# 1uO_c_v_2_2.net
KiCad netlist of a schematic drawn in EAGLE
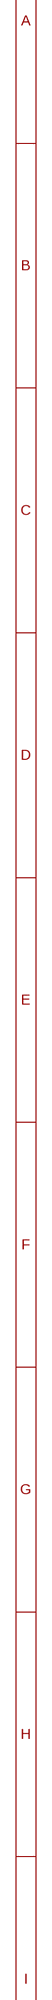
[diagram p0: schematic, sheet 1, part 1 of 2]
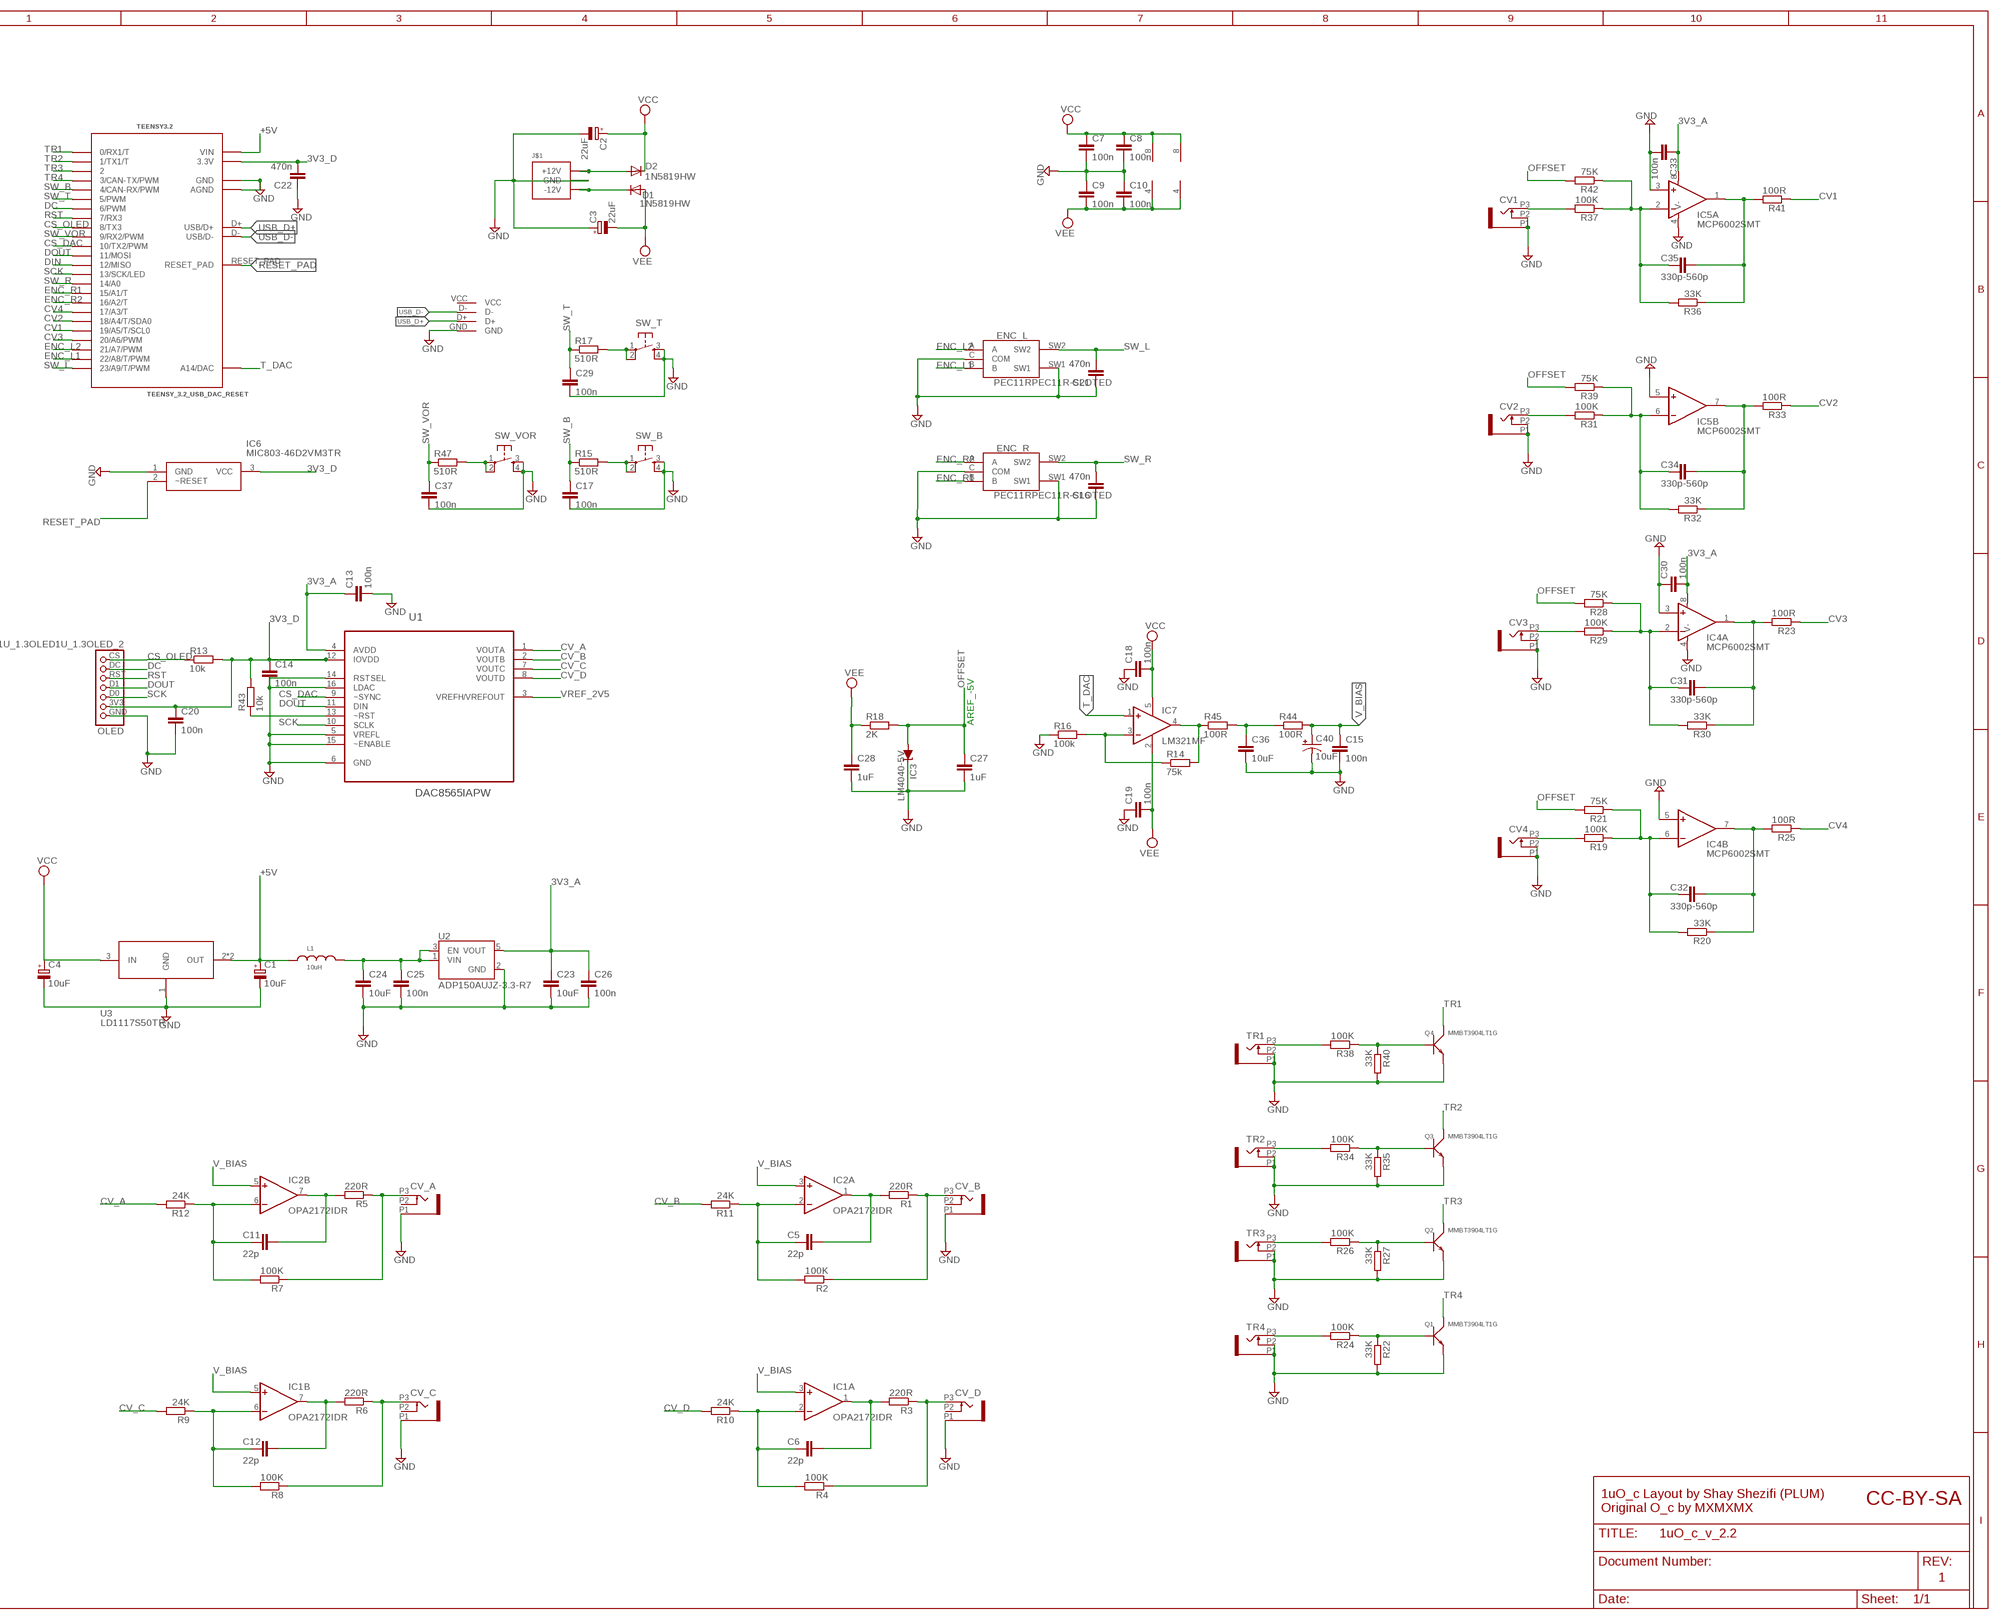
[diagram p1: schematic, sheet 1, part 2 of 2]

(export (version "E")
  (design (tool "Eeschema 10.0.6"))
  (components
    (comp (ref "C1")
      (value "10uF")
      (footprint "eagle-import:PANASONIC_B")
      (libsource (lib "eagle-import") (part "CPOL-EUB"))
    )
    (comp (ref "C2")
      (value "22uF")
      (footprint "eagle-import:PANASONIC_C")
      (libsource (lib "eagle-import") (part "CPOL-EUC"))
    )
    (comp (ref "C3")
      (value "22uF")
      (footprint "eagle-import:PANASONIC_C")
      (libsource (lib "eagle-import") (part "CPOL-EUC"))
    )
    (comp (ref "C4")
      (value "10uF")
      (footprint "eagle-import:PANASONIC_B")
      (libsource (lib "eagle-import") (part "CPOL-EUB"))
    )
    (comp (ref "C5")
      (value "22p")
      (footprint "eagle-import:C0603")
      (libsource (lib "eagle-import") (part "C-EUC0603"))
    )
    (comp (ref "C6")
      (value "22p")
      (footprint "eagle-import:C0603")
      (libsource (lib "eagle-import") (part "C-EUC0603"))
    )
    (comp (ref "C7")
      (value "100n")
      (footprint "eagle-import:C0603")
      (libsource (lib "eagle-import") (part "C-EUC0603"))
    )
    (comp (ref "C8")
      (value "100n")
      (footprint "eagle-import:C0603")
      (libsource (lib "eagle-import") (part "C-EUC0603"))
    )
    (comp (ref "C9")
      (value "100n")
      (footprint "eagle-import:C0603")
      (libsource (lib "eagle-import") (part "C-EUC0603"))
    )
    (comp (ref "C10")
      (value "100n")
      (footprint "eagle-import:C0603")
      (libsource (lib "eagle-import") (part "C-EUC0603"))
    )
    (comp (ref "C11")
      (value "22p")
      (footprint "eagle-import:C0603")
      (libsource (lib "eagle-import") (part "C-EUC0603"))
    )
    (comp (ref "C12")
      (value "22p")
      (footprint "eagle-import:C0603")
      (libsource (lib "eagle-import") (part "C-EUC0603"))
    )
    (comp (ref "C13")
      (value "100n")
      (footprint "eagle-import:C0603")
      (libsource (lib "eagle-import") (part "C-EUC0603"))
    )
    (comp (ref "C14")
      (value "100n")
      (footprint "eagle-import:C0603")
      (libsource (lib "eagle-import") (part "C-EUC0603"))
    )
    (comp (ref "C15")
      (value "100n")
      (footprint "eagle-import:C0603")
      (libsource (lib "eagle-import") (part "C-EUC0603"))
    )
    (comp (ref "C16")
      (value "470n")
      (footprint "eagle-import:C0603")
      (libsource (lib "eagle-import") (part "C-EUC0603"))
    )
    (comp (ref "C17")
      (value "100n")
      (footprint "eagle-import:C0603")
      (libsource (lib "eagle-import") (part "C-EUC0603"))
    )
    (comp (ref "C18")
      (value "100n")
      (footprint "eagle-import:C0603")
      (libsource (lib "eagle-import") (part "C-EUC0603"))
    )
    (comp (ref "C19")
      (value "100n")
      (footprint "eagle-import:C0603")
      (libsource (lib "eagle-import") (part "C-EUC0603"))
    )
    (comp (ref "C20")
      (value "100n")
      (footprint "eagle-import:C0603")
      (libsource (lib "eagle-import") (part "C-EUC0603"))
    )
    (comp (ref "C21")
      (value "470n")
      (footprint "eagle-import:C0603")
      (libsource (lib "eagle-import") (part "C-EUC0603"))
    )
    (comp (ref "C22")
      (value "470n")
      (footprint "eagle-import:C0603")
      (libsource (lib "eagle-import") (part "C-EUC0603"))
    )
    (comp (ref "C23")
      (value "10uF")
      (footprint "eagle-import:C1206K")
      (libsource (lib "eagle-import") (part "C-EUC1206K"))
    )
    (comp (ref "C24")
      (value "10uF")
      (footprint "eagle-import:C1206K")
      (libsource (lib "eagle-import") (part "C-EUC1206K"))
    )
    (comp (ref "C25")
      (value "100n")
      (footprint "eagle-import:C0603")
      (libsource (lib "eagle-import") (part "C-EUC0603"))
    )
    (comp (ref "C26")
      (value "100n")
      (footprint "eagle-import:C0603")
      (libsource (lib "eagle-import") (part "C-EUC0603"))
    )
    (comp (ref "C27")
      (value "1uF")
      (footprint "eagle-import:C0603")
      (libsource (lib "eagle-import") (part "C-EUC0603"))
    )
    (comp (ref "C28")
      (value "1uF")
      (footprint "eagle-import:C0603")
      (libsource (lib "eagle-import") (part "C-EUC0603"))
    )
    (comp (ref "C29")
      (value "100n")
      (footprint "eagle-import:C0603")
      (libsource (lib "eagle-import") (part "C-EUC0603"))
    )
    (comp (ref "C30")
      (value "100n")
      (footprint "eagle-import:C0603")
      (libsource (lib "eagle-import") (part "C-EUC0603"))
    )
    (comp (ref "C31")
      (value "330p-560p")
      (footprint "eagle-import:C0603")
      (libsource (lib "eagle-import") (part "C-EUC0603"))
    )
    (comp (ref "C32")
      (value "330p-560p")
      (footprint "eagle-import:C0603")
      (libsource (lib "eagle-import") (part "C-EUC0603"))
    )
    (comp (ref "C33")
      (value "100n")
      (footprint "eagle-import:C0603")
      (libsource (lib "eagle-import") (part "C-EUC0603"))
    )
    (comp (ref "C34")
      (value "330p-560p")
      (footprint "eagle-import:C0603")
      (libsource (lib "eagle-import") (part "C-EUC0603"))
    )
    (comp (ref "C35")
      (value "330p-560p")
      (footprint "eagle-import:C0603")
      (libsource (lib "eagle-import") (part "C-EUC0603"))
    )
    (comp (ref "C36")
      (value "10uF")
      (footprint "eagle-import:C0603")
      (libsource (lib "eagle-import") (part "C-EUC0603"))
    )
    (comp (ref "C37")
      (value "100n")
      (footprint "eagle-import:C0603")
      (libsource (lib "eagle-import") (part "C-EUC0603"))
    )
    (comp (ref "C40")
      (value "10uF")
      (footprint "eagle-import:PANASONIC_A")
      (libsource (lib "eagle-import") (part "CPOL-USA"))
    )
    (comp (ref "CV1")
      (value "OG-PJ301_PJ301_THONKICONN")
      (footprint "eagle-import:OG-PJ301_WQP_PJ_301M6_NO_HOLE")
      (libsource (lib "eagle-import") (part "OG-PJ301_PJ301_THONKICONN"))
    )
    (comp (ref "CV2")
      (value "OG-PJ301_PJ301_THONKICONN")
      (footprint "eagle-import:OG-PJ301_WQP_PJ_301M6_NO_HOLE")
      (libsource (lib "eagle-import") (part "OG-PJ301_PJ301_THONKICONN"))
    )
    (comp (ref "CV3")
      (value "OG-PJ301_PJ301_THONKICONN")
      (footprint "eagle-import:OG-PJ301_WQP_PJ_301M6_NO_HOLE")
      (libsource (lib "eagle-import") (part "OG-PJ301_PJ301_THONKICONN"))
    )
    (comp (ref "CV4")
      (value "OG-PJ301_PJ301_THONKICONN")
      (footprint "eagle-import:OG-PJ301_WQP_PJ_301M6_NO_HOLE")
      (libsource (lib "eagle-import") (part "OG-PJ301_PJ301_THONKICONN"))
    )
    (comp (ref "CV_A")
      (value "OG-PJ301_PJ301_THONKICONN")
      (footprint "eagle-import:OG-PJ301_WQP_PJ_301M6_NO_HOLE")
      (libsource (lib "eagle-import") (part "OG-PJ301_PJ301_THONKICONN"))
    )
    (comp (ref "CV_B")
      (value "OG-PJ301_PJ301_THONKICONN")
      (footprint "eagle-import:OG-PJ301_WQP_PJ_301M6_NO_HOLE")
      (libsource (lib "eagle-import") (part "OG-PJ301_PJ301_THONKICONN"))
    )
    (comp (ref "CV_C")
      (value "OG-PJ301_PJ301_THONKICONN")
      (footprint "eagle-import:OG-PJ301_WQP_PJ_301M6_NO_HOLE")
      (libsource (lib "eagle-import") (part "OG-PJ301_PJ301_THONKICONN"))
    )
    (comp (ref "CV_D")
      (value "OG-PJ301_PJ301_THONKICONN")
      (footprint "eagle-import:OG-PJ301_WQP_PJ_301M6_NO_HOLE")
      (libsource (lib "eagle-import") (part "OG-PJ301_PJ301_THONKICONN"))
    )
    (comp (ref "D1")
      (value "1N5819HW")
      (footprint "eagle-import:DIODE_SOD123")
      (libsource (lib "eagle-import") (part "DIODE_DIODE-SOD123"))
    )
    (comp (ref "D2")
      (value "1N5819HW")
      (footprint "eagle-import:DIODE_SOD123")
      (libsource (lib "eagle-import") (part "DIODE_DIODE-SOD123"))
    )
    (comp (ref "ENC_L")
      (value "PEC11RPEC11R-SLOTED")
      (footprint "eagle-import:PEC11R-SLOTED")
      (libsource (lib "eagle-import") (part "PEC11RPEC11R-SLOTED"))
    )
    (comp (ref "ENC_R")
      (value "PEC11RPEC11R-SLOTED")
      (footprint "eagle-import:PEC11R-SLOTED")
      (libsource (lib "eagle-import") (part "PEC11RPEC11R-SLOTED"))
    )
    (comp (ref "IC1")
      (value "OPA2172IDR")
      (footprint "eagle-import:SO08")
      (libsource (lib "eagle-import") (part "TL072D"))
    )
    (comp (ref "IC2")
      (value "OPA2172IDR")
      (footprint "eagle-import:SO08")
      (libsource (lib "eagle-import") (part "TL072D"))
    )
    (comp (ref "IC3")
      (value "LM4040-5V")
      (footprint "eagle-import:DBZ_R-PDSO-G3")
      (libsource (lib "eagle-import") (part "LM4041DBZB12"))
    )
    (comp (ref "IC4")
      (value "MCP6002SMT")
      (footprint "eagle-import:SOIC8")
      (libsource (lib "eagle-import") (part "MCP6002SMT"))
    )
    (comp (ref "IC5")
      (value "MCP6002SMT")
      (footprint "eagle-import:SOIC8")
      (libsource (lib "eagle-import") (part "MCP6002SMT"))
    )
    (comp (ref "IC6")
      (value "MIC803-46D2VM3TR")
      (footprint "eagle-import:SOT95P230X110-3N")
      (libsource (lib "eagle-import") (part "MIC803-46D2VM3TR"))
    )
    (comp (ref "IC7")
      (value "LM321MF")
      (footprint "eagle-import:SOT23-5")
      (libsource (lib "eagle-import") (part "LM321?MF"))
    )
    (comp (ref "J$1")
      (value "POWER_SIMPLE10")
      (footprint "eagle-import:POWER_10")
      (libsource (lib "eagle-import") (part "POWER_SIMPLE10"))
    )
    (comp (ref "L1")
      (value "10uH")
      (footprint "eagle-import:WE-LQ_M")
      (libsource (lib "eagle-import") (part "WE-LQ_1210_744032001"))
    )
    (comp (ref "OLED")
      (value "1U_1.3OLED1U_1.3OLED_2")
      (footprint "eagle-import:1U_1.3OLED_2")
      (libsource (lib "eagle-import") (part "1U_1.3OLED1U_1.3OLED_2"))
    )
    (comp (ref "Q1")
      (value "MMBT3904LT1G")
      (footprint "eagle-import:SOT-23")
      (libsource (lib "eagle-import") (part "SMD-TRANSISTORS-NPN-40V-200MA-MMBT3904LT1G(SOT-23)"))
    )
    (comp (ref "Q2")
      (value "MMBT3904LT1G")
      (footprint "eagle-import:SOT-23")
      (libsource (lib "eagle-import") (part "SMD-TRANSISTORS-NPN-40V-200MA-MMBT3904LT1G(SOT-23)"))
    )
    (comp (ref "Q3")
      (value "MMBT3904LT1G")
      (footprint "eagle-import:SOT-23")
      (libsource (lib "eagle-import") (part "SMD-TRANSISTORS-NPN-40V-200MA-MMBT3904LT1G(SOT-23)"))
    )
    (comp (ref "Q4")
      (value "MMBT3904LT1G")
      (footprint "eagle-import:SOT-23")
      (libsource (lib "eagle-import") (part "SMD-TRANSISTORS-NPN-40V-200MA-MMBT3904LT1G(SOT-23)"))
    )
    (comp (ref "R1")
      (value "220R")
      (footprint "eagle-import:R0603")
      (libsource (lib "eagle-import") (part "R-EU_R0603"))
    )
    (comp (ref "R2")
      (value "100K")
      (footprint "eagle-import:R0603")
      (libsource (lib "eagle-import") (part "R-EU_R0603"))
    )
    (comp (ref "R3")
      (value "220R")
      (footprint "eagle-import:R0603")
      (libsource (lib "eagle-import") (part "R-EU_R0603"))
    )
    (comp (ref "R4")
      (value "100K")
      (footprint "eagle-import:R0603")
      (libsource (lib "eagle-import") (part "R-EU_R0603"))
    )
    (comp (ref "R5")
      (value "220R")
      (footprint "eagle-import:R0603")
      (libsource (lib "eagle-import") (part "R-EU_R0603"))
    )
    (comp (ref "R6")
      (value "220R")
      (footprint "eagle-import:R0603")
      (libsource (lib "eagle-import") (part "R-EU_R0603"))
    )
    (comp (ref "R7")
      (value "100K")
      (footprint "eagle-import:R0603")
      (libsource (lib "eagle-import") (part "R-EU_R0603"))
    )
    (comp (ref "R8")
      (value "100K")
      (footprint "eagle-import:R0603")
      (libsource (lib "eagle-import") (part "R-EU_R0603"))
    )
    (comp (ref "R9")
      (value "24K")
      (footprint "eagle-import:R0603")
      (libsource (lib "eagle-import") (part "R-EU_R0603"))
    )
    (comp (ref "R10")
      (value "24K")
      (footprint "eagle-import:R0603")
      (libsource (lib "eagle-import") (part "R-EU_R0603"))
    )
    (comp (ref "R11")
      (value "24K")
      (footprint "eagle-import:R0603")
      (libsource (lib "eagle-import") (part "R-EU_R0603"))
    )
    (comp (ref "R12")
      (value "24K")
      (footprint "eagle-import:R0603")
      (libsource (lib "eagle-import") (part "R-EU_R0603"))
    )
    (comp (ref "R13")
      (value "10k")
      (footprint "eagle-import:R0603")
      (libsource (lib "eagle-import") (part "R-EU_R0603"))
    )
    (comp (ref "R14")
      (value "75k")
      (footprint "eagle-import:R0603")
      (libsource (lib "eagle-import") (part "R-EU_R0603"))
    )
    (comp (ref "R15")
      (value "510R")
      (footprint "eagle-import:R0603")
      (libsource (lib "eagle-import") (part "R-EU_R0603"))
    )
    (comp (ref "R16")
      (value "100k")
      (footprint "eagle-import:R0603")
      (libsource (lib "eagle-import") (part "R-EU_R0603"))
    )
    (comp (ref "R17")
      (value "510R")
      (footprint "eagle-import:R0603")
      (libsource (lib "eagle-import") (part "R-EU_R0603"))
    )
    (comp (ref "R18")
      (value "2K")
      (footprint "eagle-import:R0603")
      (libsource (lib "eagle-import") (part "R-EU_R0603"))
    )
    (comp (ref "R19")
      (value "100K")
      (footprint "eagle-import:R0603")
      (libsource (lib "eagle-import") (part "R-EU_R0603"))
    )
    (comp (ref "R20")
      (value "33K")
      (footprint "eagle-import:R0603")
      (libsource (lib "eagle-import") (part "R-EU_R0603"))
    )
    (comp (ref "R21")
      (value "75K")
      (footprint "eagle-import:R0603")
      (libsource (lib "eagle-import") (part "R-EU_R0603"))
    )
    (comp (ref "R22")
      (value "33K")
      (footprint "eagle-import:R0603")
      (libsource (lib "eagle-import") (part "R-EU_R0603"))
    )
    (comp (ref "R23")
      (value "100R")
      (footprint "eagle-import:R0603")
      (libsource (lib "eagle-import") (part "R-EU_R0603"))
    )
    (comp (ref "R24")
      (value "100K")
      (footprint "eagle-import:R0603")
      (libsource (lib "eagle-import") (part "R-EU_R0603"))
    )
    (comp (ref "R25")
      (value "100R")
      (footprint "eagle-import:R0603")
      (libsource (lib "eagle-import") (part "R-EU_R0603"))
    )
    (comp (ref "R26")
      (value "100K")
      (footprint "eagle-import:R0603")
      (libsource (lib "eagle-import") (part "R-EU_R0603"))
    )
    (comp (ref "R27")
      (value "33K")
      (footprint "eagle-import:R0603")
      (libsource (lib "eagle-import") (part "R-EU_R0603"))
    )
    (comp (ref "R28")
      (value "75K")
      (footprint "eagle-import:R0603")
      (libsource (lib "eagle-import") (part "R-EU_R0603"))
    )
    (comp (ref "R29")
      (value "100K")
      (footprint "eagle-import:R0603")
      (libsource (lib "eagle-import") (part "R-EU_R0603"))
    )
    (comp (ref "R30")
      (value "33K")
      (footprint "eagle-import:R0603")
      (libsource (lib "eagle-import") (part "R-EU_R0603"))
    )
    (comp (ref "R31")
      (value "100K")
      (footprint "eagle-import:R0603")
      (libsource (lib "eagle-import") (part "R-EU_R0603"))
    )
    (comp (ref "R32")
      (value "33K")
      (footprint "eagle-import:R0603")
      (libsource (lib "eagle-import") (part "R-EU_R0603"))
    )
    (comp (ref "R33")
      (value "100R")
      (footprint "eagle-import:R0603")
      (libsource (lib "eagle-import") (part "R-EU_R0603"))
    )
    (comp (ref "R34")
      (value "100K")
      (footprint "eagle-import:R0603")
      (libsource (lib "eagle-import") (part "R-EU_R0603"))
    )
    (comp (ref "R35")
      (value "33K")
      (footprint "eagle-import:R0603")
      (libsource (lib "eagle-import") (part "R-EU_R0603"))
    )
    (comp (ref "R36")
      (value "33K")
      (footprint "eagle-import:R0603")
      (libsource (lib "eagle-import") (part "R-EU_R0603"))
    )
    (comp (ref "R37")
      (value "100K")
      (footprint "eagle-import:R0603")
      (libsource (lib "eagle-import") (part "R-EU_R0603"))
    )
    (comp (ref "R38")
      (value "100K")
      (footprint "eagle-import:R0603")
      (libsource (lib "eagle-import") (part "R-EU_R0603"))
    )
    (comp (ref "R39")
      (value "75K")
      (footprint "eagle-import:R0603")
      (libsource (lib "eagle-import") (part "R-EU_R0603"))
    )
    (comp (ref "R40")
      (value "33K")
      (footprint "eagle-import:R0603")
      (libsource (lib "eagle-import") (part "R-EU_R0603"))
    )
    (comp (ref "R41")
      (value "100R")
      (footprint "eagle-import:R0603")
      (libsource (lib "eagle-import") (part "R-EU_R0603"))
    )
    (comp (ref "R42")
      (value "75K")
      (footprint "eagle-import:R0603")
      (libsource (lib "eagle-import") (part "R-EU_R0603"))
    )
    (comp (ref "R43")
      (value "10k")
      (footprint "eagle-import:R0603")
      (libsource (lib "eagle-import") (part "R-EU_R0603"))
    )
    (comp (ref "R44")
      (value "100R")
      (footprint "eagle-import:R0603")
      (libsource (lib "eagle-import") (part "R-EU_R0603"))
    )
    (comp (ref "R45")
      (value "100R")
      (footprint "eagle-import:R0603")
      (libsource (lib "eagle-import") (part "R-EU_R0603"))
    )
    (comp (ref "R47")
      (value "510R")
      (footprint "eagle-import:R0603")
      (libsource (lib "eagle-import") (part "R-EU_R0603"))
    )
    (comp (ref "SW_B")
      (value "TAC_SWITCHPTH")
      (footprint "eagle-import:TACTILE-PTH")
      (libsource (lib "eagle-import") (part "TAC_SWITCHPTH"))
    )
    (comp (ref "SW_T")
      (value "TAC_SWITCHPTH")
      (footprint "eagle-import:TACTILE-PTH")
      (libsource (lib "eagle-import") (part "TAC_SWITCHPTH"))
    )
    (comp (ref "SW_VOR")
      (value "TAC_SWITCHPTH")
      (footprint "eagle-import:TACTILE-PTH")
      (libsource (lib "eagle-import") (part "TAC_SWITCHPTH"))
    )
    (comp (ref "TEENSY3.2")
      (value "TEENSY_3.2_USB_DAC_RESET")
      (footprint "eagle-import:TEENSY_3.2_USB_DAC_RESET")
      (libsource (lib "eagle-import") (part "TEENSY_3.2_USB_DAC_RESET"))
    )
    (comp (ref "TR1")
      (value "OG-PJ301_PJ301_THONKICONN")
      (footprint "eagle-import:OG-PJ301_WQP_PJ_301M6_NO_HOLE")
      (libsource (lib "eagle-import") (part "OG-PJ301_PJ301_THONKICONN"))
    )
    (comp (ref "TR2")
      (value "OG-PJ301_PJ301_THONKICONN")
      (footprint "eagle-import:OG-PJ301_WQP_PJ_301M6_NO_HOLE")
      (libsource (lib "eagle-import") (part "OG-PJ301_PJ301_THONKICONN"))
    )
    (comp (ref "TR3")
      (value "OG-PJ301_PJ301_THONKICONN")
      (footprint "eagle-import:OG-PJ301_WQP_PJ_301M6_NO_HOLE")
      (libsource (lib "eagle-import") (part "OG-PJ301_PJ301_THONKICONN"))
    )
    (comp (ref "TR4")
      (value "OG-PJ301_PJ301_THONKICONN")
      (footprint "eagle-import:OG-PJ301_WQP_PJ_301M6_NO_HOLE")
      (libsource (lib "eagle-import") (part "OG-PJ301_PJ301_THONKICONN"))
    )
    (comp (ref "U$1")
      (value "USB_BOARD")
      (footprint "eagle-import:MICRO-USB-BOARD")
      (libsource (lib "eagle-import") (part "USB_BOARD"))
    )
    (comp (ref "U1")
      (value "DAC8565IAPW")
      (footprint "eagle-import:SOP65P640X120-16N")
      (fields (field (name "MF") "Texas Instruments"))
      (libsource (lib "eagle-import") (part "DAC8565IAPW"))
    )
    (comp (ref "U2")
      (value "ADP150AUJZ-3.3-R7")
      (footprint "eagle-import:SOT95P280X100-5N")
      (fields (field (name "MF") "Analog Devices") (field (name "MP") "ADP150AUJZ-2.0-R7"))
      (libsource (lib "eagle-import") (part "ADP150AUJZ-3.3-R7"))
    )
    (comp (ref "U3")
      (value "LD1117S50TR")
      (footprint "eagle-import:SOT223")
      (fields (field (name "MF") "STMicroelectronics"))
      (libsource (lib "eagle-import") (part "LD1117S50TR"))
    )
  )
  (nets
    (net (code "1") (name "/+5V") (class "Default")
      (node (ref "C1") (pin "+") (pinfunction "+_+") (pintype "passive"))
      (node (ref "L1") (pin "1") (pinfunction "1_1") (pintype "passive"))
      (node (ref "TEENSY3.2") (pin "VIN") (pinfunction "VIN_VIN") (pintype "power_in"))
      (node (ref "U3") (pin "2") (pinfunction "OUT_2") (pintype "output"))
      (node (ref "U3") (pin "4") (pinfunction "OUT_4") (pintype "output"))
    )
    (net (code "2") (name "/3V3_A") (class "Default")
      (node (ref "C13") (pin "1") (pinfunction "1_1") (pintype "passive"))
      (node (ref "C23") (pin "1") (pinfunction "1_1") (pintype "passive"))
      (node (ref "C26") (pin "1") (pinfunction "1_1") (pintype "passive"))
      (node (ref "C30") (pin "2") (pinfunction "2_2") (pintype "passive"))
      (node (ref "C33") (pin "1") (pinfunction "1_1") (pintype "passive"))
      (node (ref "IC4") (pin "8") (pinfunction "V+_8") (pintype "power_in"))
      (node (ref "IC5") (pin "8") (pinfunction "V+_8") (pintype "power_in"))
      (node (ref "U1") (pin "4") (pinfunction "AVDD_4") (pintype "power_in"))
      (node (ref "U2") (pin "5") (pinfunction "VOUT_5") (pintype "output"))
    )
    (net (code "3") (name "/3V3_D") (class "Default")
      (node (ref "C14") (pin "1") (pinfunction "1_1") (pintype "passive"))
      (node (ref "C20") (pin "1") (pinfunction "1_1") (pintype "passive"))
      (node (ref "C22") (pin "2") (pinfunction "2_2") (pintype "passive"))
      (node (ref "IC6") (pin "3") (pinfunction "VCC_3") (pintype "bidirectional"))
      (node (ref "OLED") (pin "3V3") (pinfunction "3V3_3V3") (pintype "passive"))
      (node (ref "R13") (pin "2") (pinfunction "2_2") (pintype "passive"))
      (node (ref "R43") (pin "2") (pinfunction "2_2") (pintype "passive"))
      (node (ref "TEENSY3.2") (pin "3.3V") (pinfunction "3.3V_3.3V") (pintype "power_in"))
      (node (ref "U1") (pin "12") (pinfunction "IOVDD_12") (pintype "power_in"))
    )
    (net (code "4") (name "/CS_DAC") (class "Default")
      (node (ref "TEENSY3.2") (pin "10") (pinfunction "10/TX2/PWM_10") (pintype "bidirectional"))
      (node (ref "U1") (pin "9") (pinfunction "~{SYNC}_9") (pintype "input"))
    )
    (net (code "5") (name "/CS_OLED") (class "Default")
      (node (ref "OLED") (pin "CS") (pinfunction "CS_CS") (pintype "passive"))
      (node (ref "R13") (pin "1") (pinfunction "1_1") (pintype "passive"))
      (node (ref "TEENSY3.2") (pin "8") (pinfunction "8/TX3_8") (pintype "bidirectional"))
    )
    (net (code "6") (name "/CV1") (class "Default")
      (node (ref "R41") (pin "1") (pinfunction "1_1") (pintype "passive"))
      (node (ref "TEENSY3.2") (pin "19/A5") (pinfunction "19/A5/T/SCL0_19/A5") (pintype "bidirectional"))
    )
    (net (code "7") (name "/CV2") (class "Default")
      (node (ref "R33") (pin "1") (pinfunction "1_1") (pintype "passive"))
      (node (ref "TEENSY3.2") (pin "18/A4") (pinfunction "18/A4/T/SDA0_18/A4") (pintype "bidirectional"))
    )
    (net (code "8") (name "/CV3") (class "Default")
      (node (ref "R23") (pin "1") (pinfunction "1_1") (pintype "passive"))
      (node (ref "TEENSY3.2") (pin "20/A6") (pinfunction "20/A6/PWM_20/A6") (pintype "bidirectional"))
    )
    (net (code "9") (name "/CV4") (class "Default")
      (node (ref "R25") (pin "1") (pinfunction "1_1") (pintype "passive"))
      (node (ref "TEENSY3.2") (pin "17/A3") (pinfunction "17/A3/T_17/A3") (pintype "bidirectional"))
    )
    (net (code "10") (name "/CV_A") (class "Default")
      (node (ref "R12") (pin "2") (pinfunction "2_2") (pintype "passive"))
      (node (ref "U1") (pin "1") (pinfunction "VOUTA_1") (pintype "output"))
    )
    (net (code "11") (name "/CV_B") (class "Default")
      (node (ref "R11") (pin "2") (pinfunction "2_2") (pintype "passive"))
      (node (ref "U1") (pin "2") (pinfunction "VOUTB_2") (pintype "output"))
    )
    (net (code "12") (name "/CV_C") (class "Default")
      (node (ref "R9") (pin "2") (pinfunction "2_2") (pintype "passive"))
      (node (ref "U1") (pin "7") (pinfunction "VOUTC_7") (pintype "output"))
    )
    (net (code "13") (name "/CV_D") (class "Default")
      (node (ref "R10") (pin "2") (pinfunction "2_2") (pintype "passive"))
      (node (ref "U1") (pin "8") (pinfunction "VOUTD_8") (pintype "output"))
    )
    (net (code "14") (name "/DC") (class "Default")
      (node (ref "OLED") (pin "DC") (pinfunction "DC_DC") (pintype "passive"))
      (node (ref "TEENSY3.2") (pin "6") (pinfunction "6/PWM_6") (pintype "bidirectional"))
    )
    (net (code "15") (name "/DIN") (class "Default")
      (node (ref "TEENSY3.2") (pin "12") (pinfunction "12/MISO_12") (pintype "bidirectional"))
    )
    (net (code "16") (name "/DOUT") (class "Default")
      (node (ref "OLED") (pin "D1") (pinfunction "D1_D1") (pintype "passive"))
      (node (ref "TEENSY3.2") (pin "11") (pinfunction "11/MOSI_11") (pintype "bidirectional"))
      (node (ref "U1") (pin "11") (pinfunction "DIN_11") (pintype "input"))
    )
    (net (code "17") (name "/ENC_L1") (class "Default")
      (node (ref "ENC_L") (pin "B") (pinfunction "B_B") (pintype "bidirectional"))
      (node (ref "TEENSY3.2") (pin "22/A8") (pinfunction "22/A8/T/PWM_22/A8") (pintype "bidirectional"))
    )
    (net (code "18") (name "/ENC_L2") (class "Default")
      (node (ref "ENC_L") (pin "A") (pinfunction "A_A") (pintype "bidirectional"))
      (node (ref "TEENSY3.2") (pin "21/A7") (pinfunction "21/A7/PWM_21/A7") (pintype "bidirectional"))
    )
    (net (code "19") (name "/ENC_R1") (class "Default")
      (node (ref "ENC_R") (pin "B") (pinfunction "B_B") (pintype "bidirectional"))
      (node (ref "TEENSY3.2") (pin "15/A1") (pinfunction "15/A1/T_15/A1") (pintype "bidirectional"))
    )
    (net (code "20") (name "/ENC_R2") (class "Default")
      (node (ref "ENC_R") (pin "A") (pinfunction "A_A") (pintype "bidirectional"))
      (node (ref "TEENSY3.2") (pin "16/A2") (pinfunction "16/A2/T_16/A2") (pintype "bidirectional"))
    )
    (net (code "21") (name "/OFFSET") (class "Default")
      (node (ref "C27") (pin "1") (pinfunction "1_1") (pintype "passive"))
      (node (ref "IC3") (pin "2") (pinfunction "A_2") (pintype "passive"))
      (node (ref "R18") (pin "2") (pinfunction "2_2") (pintype "passive"))
      (node (ref "R21") (pin "2") (pinfunction "2_2") (pintype "passive"))
      (node (ref "R28") (pin "2") (pinfunction "2_2") (pintype "passive"))
      (node (ref "R39") (pin "2") (pinfunction "2_2") (pintype "passive"))
      (node (ref "R42") (pin "2") (pinfunction "2_2") (pintype "passive"))
    )
    (net (code "22") (name "/RST") (class "Default")
      (node (ref "OLED") (pin "RST") (pinfunction "RST_RST") (pintype "passive"))
      (node (ref "TEENSY3.2") (pin "7") (pinfunction "7/RX3_7") (pintype "bidirectional"))
    )
    (net (code "23") (name "/SCK") (class "Default")
      (node (ref "OLED") (pin "D0") (pinfunction "D0_D0") (pintype "passive"))
      (node (ref "TEENSY3.2") (pin "13") (pinfunction "13/SCK/LED_13") (pintype "bidirectional"))
      (node (ref "U1") (pin "10") (pinfunction "SCLK_10") (pintype "input"))
    )
    (net (code "24") (name "/SW_B") (class "Default")
      (node (ref "C17") (pin "1") (pinfunction "1_1") (pintype "passive"))
      (node (ref "R15") (pin "1") (pinfunction "1_1") (pintype "passive"))
      (node (ref "TEENSY3.2") (pin "4") (pinfunction "4/CAN-RX/PWM_4") (pintype "bidirectional"))
    )
    (net (code "25") (name "/SW_L") (class "Default")
      (node (ref "C21") (pin "2") (pinfunction "2_2") (pintype "passive"))
      (node (ref "ENC_L") (pin "SW2") (pinfunction "SW2_SW2") (pintype "bidirectional"))
      (node (ref "TEENSY3.2") (pin "23/A9") (pinfunction "23/A9/T/PWM_23/A9") (pintype "bidirectional"))
    )
    (net (code "26") (name "/SW_R") (class "Default")
      (node (ref "C16") (pin "2") (pinfunction "2_2") (pintype "passive"))
      (node (ref "ENC_R") (pin "SW2") (pinfunction "SW2_SW2") (pintype "bidirectional"))
      (node (ref "TEENSY3.2") (pin "14/A0") (pinfunction "14/A0_14/A0") (pintype "bidirectional"))
    )
    (net (code "27") (name "/SW_T") (class "Default")
      (node (ref "C29") (pin "1") (pinfunction "1_1") (pintype "passive"))
      (node (ref "R17") (pin "1") (pinfunction "1_1") (pintype "passive"))
      (node (ref "TEENSY3.2") (pin "5") (pinfunction "5/PWM_5") (pintype "bidirectional"))
    )
    (net (code "28") (name "/SW_VOR") (class "Default")
      (node (ref "C37") (pin "1") (pinfunction "1_1") (pintype "passive"))
      (node (ref "R47") (pin "1") (pinfunction "1_1") (pintype "passive"))
      (node (ref "TEENSY3.2") (pin "9") (pinfunction "9/RX2/PWM_9") (pintype "bidirectional"))
    )
    (net (code "29") (name "/TR1") (class "Default")
      (node (ref "Q4") (pin "3") (pinfunction "C_3") (pintype "passive"))
      (node (ref "TEENSY3.2") (pin "0") (pinfunction "0/RX1/T_0") (pintype "bidirectional"))
    )
    (net (code "30") (name "/TR2") (class "Default")
      (node (ref "Q3") (pin "3") (pinfunction "C_3") (pintype "passive"))
      (node (ref "TEENSY3.2") (pin "1") (pinfunction "1/TX1/T_1") (pintype "bidirectional"))
    )
    (net (code "31") (name "/TR3") (class "Default")
      (node (ref "Q2") (pin "3") (pinfunction "C_3") (pintype "passive"))
      (node (ref "TEENSY3.2") (pin "2") (pinfunction "2_2") (pintype "bidirectional"))
    )
    (net (code "32") (name "/TR4") (class "Default")
      (node (ref "Q1") (pin "3") (pinfunction "C_3") (pintype "passive"))
      (node (ref "TEENSY3.2") (pin "3") (pinfunction "3/CAN-TX/PWM_3") (pintype "bidirectional"))
    )
    (net (code "33") (name "/VREF_2V5") (class "Default")
      (node (ref "U1") (pin "3") (pinfunction "VREFH/VREFOUT_3") (pintype "bidirectional"))
    )
    (net (code "34") (name "GND") (class "Default")
      (node (ref "C1") (pin "-") (pinfunction "-_-") (pintype "passive"))
      (node (ref "C10") (pin "1") (pinfunction "1_1") (pintype "passive"))
      (node (ref "C13") (pin "2") (pinfunction "2_2") (pintype "passive"))
      (node (ref "C14") (pin "2") (pinfunction "2_2") (pintype "passive"))
      (node (ref "C15") (pin "2") (pinfunction "2_2") (pintype "passive"))
      (node (ref "C16") (pin "1") (pinfunction "1_1") (pintype "passive"))
      (node (ref "C17") (pin "2") (pinfunction "2_2") (pintype "passive"))
      (node (ref "C18") (pin "1") (pinfunction "1_1") (pintype "passive"))
      (node (ref "C19") (pin "1") (pinfunction "1_1") (pintype "passive"))
      (node (ref "C2") (pin "-") (pinfunction "-_-") (pintype "passive"))
      (node (ref "C20") (pin "2") (pinfunction "2_2") (pintype "passive"))
      (node (ref "C21") (pin "1") (pinfunction "1_1") (pintype "passive"))
      (node (ref "C22") (pin "1") (pinfunction "1_1") (pintype "passive"))
      (node (ref "C23") (pin "2") (pinfunction "2_2") (pintype "passive"))
      (node (ref "C24") (pin "2") (pinfunction "2_2") (pintype "passive"))
      (node (ref "C25") (pin "2") (pinfunction "2_2") (pintype "passive"))
      (node (ref "C26") (pin "2") (pinfunction "2_2") (pintype "passive"))
      (node (ref "C27") (pin "2") (pinfunction "2_2") (pintype "passive"))
      (node (ref "C28") (pin "2") (pinfunction "2_2") (pintype "passive"))
      (node (ref "C29") (pin "2") (pinfunction "2_2") (pintype "passive"))
      (node (ref "C3") (pin "+") (pinfunction "+_+") (pintype "passive"))
      (node (ref "C30") (pin "1") (pinfunction "1_1") (pintype "passive"))
      (node (ref "C33") (pin "2") (pinfunction "2_2") (pintype "passive"))
      (node (ref "C36") (pin "2") (pinfunction "2_2") (pintype "passive"))
      (node (ref "C37") (pin "2") (pinfunction "2_2") (pintype "passive"))
      (node (ref "C4") (pin "-") (pinfunction "-_-") (pintype "passive"))
      (node (ref "C40") (pin "-") (pinfunction "-_-") (pintype "passive"))
      (node (ref "C7") (pin "2") (pinfunction "2_2") (pintype "passive"))
      (node (ref "C8") (pin "2") (pinfunction "2_2") (pintype "passive"))
      (node (ref "C9") (pin "1") (pinfunction "1_1") (pintype "passive"))
      (node (ref "CV1") (pin "P1") (pinfunction "1_P1") (pintype "passive"))
      (node (ref "CV1") (pin "P2") (pinfunction "2_P2") (pintype "passive"))
      (node (ref "CV2") (pin "P1") (pinfunction "1_P1") (pintype "passive"))
      (node (ref "CV2") (pin "P2") (pinfunction "2_P2") (pintype "passive"))
      (node (ref "CV3") (pin "P1") (pinfunction "1_P1") (pintype "passive"))
      (node (ref "CV3") (pin "P2") (pinfunction "2_P2") (pintype "passive"))
      (node (ref "CV4") (pin "P1") (pinfunction "1_P1") (pintype "passive"))
      (node (ref "CV4") (pin "P2") (pinfunction "2_P2") (pintype "passive"))
      (node (ref "CV_A") (pin "P1") (pinfunction "1_P1") (pintype "passive"))
      (node (ref "CV_B") (pin "P1") (pinfunction "1_P1") (pintype "passive"))
      (node (ref "CV_C") (pin "P1") (pinfunction "1_P1") (pintype "passive"))
      (node (ref "CV_D") (pin "P1") (pinfunction "1_P1") (pintype "passive"))
      (node (ref "ENC_L") (pin "C") (pinfunction "COM_C") (pintype "bidirectional"))
      (node (ref "ENC_L") (pin "SW1") (pinfunction "SW1_SW1") (pintype "bidirectional"))
      (node (ref "ENC_R") (pin "C") (pinfunction "COM_C") (pintype "bidirectional"))
      (node (ref "ENC_R") (pin "SW1") (pinfunction "SW1_SW1") (pintype "bidirectional"))
      (node (ref "IC3") (pin "1") (pinfunction "C_1") (pintype "passive"))
      (node (ref "IC4") (pin "3") (pinfunction "+IN_3") (pintype "input"))
      (node (ref "IC4") (pin "4") (pinfunction "V-_4") (pintype "power_in"))
      (node (ref "IC4") (pin "5") (pinfunction "+IN_5") (pintype "input"))
      (node (ref "IC5") (pin "3") (pinfunction "+IN_3") (pintype "input"))
      (node (ref "IC5") (pin "4") (pinfunction "V-_4") (pintype "power_in"))
      (node (ref "IC5") (pin "5") (pinfunction "+IN_5") (pintype "input"))
      (node (ref "IC6") (pin "1") (pinfunction "GND_1") (pintype "bidirectional"))
      (node (ref "J$1") (pin "3") (pinfunction "GND_3") (pintype "bidirectional"))
      (node (ref "J$1") (pin "4") (pinfunction "GND_4") (pintype "bidirectional"))
      (node (ref "J$1") (pin "5") (pinfunction "GND_5") (pintype "bidirectional"))
      (node (ref "J$1") (pin "6") (pinfunction "GND_6") (pintype "bidirectional"))
      (node (ref "J$1") (pin "7") (pinfunction "GND_7") (pintype "bidirectional"))
      (node (ref "J$1") (pin "8") (pinfunction "GND_8") (pintype "bidirectional"))
      (node (ref "OLED") (pin "GND") (pinfunction "GND_GND") (pintype "passive"))
      (node (ref "Q1") (pin "2") (pinfunction "E_2") (pintype "passive"))
      (node (ref "Q2") (pin "2") (pinfunction "E_2") (pintype "passive"))
      (node (ref "Q3") (pin "2") (pinfunction "E_2") (pintype "passive"))
      (node (ref "Q4") (pin "2") (pinfunction "E_2") (pintype "passive"))
      (node (ref "R16") (pin "1") (pinfunction "1_1") (pintype "passive"))
      (node (ref "R22") (pin "2") (pinfunction "2_2") (pintype "passive"))
      (node (ref "R27") (pin "2") (pinfunction "2_2") (pintype "passive"))
      (node (ref "R35") (pin "2") (pinfunction "2_2") (pintype "passive"))
      (node (ref "R40") (pin "2") (pinfunction "2_2") (pintype "passive"))
      (node (ref "SW_B") (pin "3") (pinfunction "3_3") (pintype "passive"))
      (node (ref "SW_B") (pin "4") (pinfunction "4_4") (pintype "passive"))
      (node (ref "SW_T") (pin "3") (pinfunction "3_3") (pintype "passive"))
      (node (ref "SW_T") (pin "4") (pinfunction "4_4") (pintype "passive"))
      (node (ref "SW_VOR") (pin "3") (pinfunction "3_3") (pintype "passive"))
      (node (ref "SW_VOR") (pin "4") (pinfunction "4_4") (pintype "passive"))
      (node (ref "TEENSY3.2") (pin "AGND") (pinfunction "AGND_AGND") (pintype "power_in"))
      (node (ref "TEENSY3.2") (pin "GND") (pinfunction "GND_GND") (pintype "power_in"))
      (node (ref "TR1") (pin "P1") (pinfunction "1_P1") (pintype "passive"))
      (node (ref "TR1") (pin "P2") (pinfunction "2_P2") (pintype "passive"))
      (node (ref "TR2") (pin "P1") (pinfunction "1_P1") (pintype "passive"))
      (node (ref "TR2") (pin "P2") (pinfunction "2_P2") (pintype "passive"))
      (node (ref "TR3") (pin "P1") (pinfunction "1_P1") (pintype "passive"))
      (node (ref "TR3") (pin "P2") (pinfunction "2_P2") (pintype "passive"))
      (node (ref "TR4") (pin "P1") (pinfunction "1_P1") (pintype "passive"))
      (node (ref "TR4") (pin "P2") (pinfunction "2_P2") (pintype "passive"))
      (node (ref "U$1") (pin "GND") (pinfunction "GND_GND") (pintype "bidirectional"))
      (node (ref "U1") (pin "14") (pinfunction "RSTSEL_14") (pintype "input"))
      (node (ref "U1") (pin "15") (pinfunction "~{ENABLE}_15") (pintype "input"))
      (node (ref "U1") (pin "16") (pinfunction "LDAC_16") (pintype "input"))
      (node (ref "U1") (pin "5") (pinfunction "VREFL_5") (pintype "input"))
      (node (ref "U1") (pin "6") (pinfunction "GND_6") (pintype "passive"))
      (node (ref "U2") (pin "2") (pinfunction "GND_2") (pintype "power_in"))
      (node (ref "U3") (pin "1") (pinfunction "GND_1") (pintype "passive"))
    )
    (net (code "35") (name "Net-(C36-Pad1)") (class "Default")
      (node (ref "C36") (pin "1") (pinfunction "1_1") (pintype "passive"))
      (node (ref "R44") (pin "1") (pinfunction "1_1") (pintype "passive"))
      (node (ref "R45") (pin "2") (pinfunction "2_2") (pintype "passive"))
    )
    (net (code "36") (name "Net-(CV1-3)") (class "Default")
      (node (ref "CV1") (pin "P3") (pinfunction "3_P3") (pintype "passive"))
      (node (ref "R37") (pin "2") (pinfunction "2_2") (pintype "passive"))
    )
    (net (code "37") (name "Net-(CV2-3)") (class "Default")
      (node (ref "CV2") (pin "P3") (pinfunction "3_P3") (pintype "passive"))
      (node (ref "R31") (pin "2") (pinfunction "2_2") (pintype "passive"))
    )
    (net (code "38") (name "Net-(CV3-3)") (class "Default")
      (node (ref "CV3") (pin "P3") (pinfunction "3_P3") (pintype "passive"))
      (node (ref "R29") (pin "2") (pinfunction "2_2") (pintype "passive"))
    )
    (net (code "39") (name "Net-(CV4-3)") (class "Default")
      (node (ref "CV4") (pin "P3") (pinfunction "3_P3") (pintype "passive"))
      (node (ref "R19") (pin "2") (pinfunction "2_2") (pintype "passive"))
    )
    (net (code "40") (name "Net-(CV_A-3)") (class "Default")
      (node (ref "CV_A") (pin "P3") (pinfunction "3_P3") (pintype "passive"))
      (node (ref "R5") (pin "1") (pinfunction "1_1") (pintype "passive"))
      (node (ref "R7") (pin "1") (pinfunction "1_1") (pintype "passive"))
    )
    (net (code "41") (name "Net-(CV_B-3)") (class "Default")
      (node (ref "CV_B") (pin "P3") (pinfunction "3_P3") (pintype "passive"))
      (node (ref "R1") (pin "1") (pinfunction "1_1") (pintype "passive"))
      (node (ref "R2") (pin "1") (pinfunction "1_1") (pintype "passive"))
    )
    (net (code "42") (name "Net-(CV_C-3)") (class "Default")
      (node (ref "CV_C") (pin "P3") (pinfunction "3_P3") (pintype "passive"))
      (node (ref "R6") (pin "1") (pinfunction "1_1") (pintype "passive"))
      (node (ref "R8") (pin "1") (pinfunction "1_1") (pintype "passive"))
    )
    (net (code "43") (name "Net-(CV_D-3)") (class "Default")
      (node (ref "CV_D") (pin "P3") (pinfunction "3_P3") (pintype "passive"))
      (node (ref "R3") (pin "1") (pinfunction "1_1") (pintype "passive"))
      (node (ref "R4") (pin "1") (pinfunction "1_1") (pintype "passive"))
    )
    (net (code "44") (name "Net-(D1-PadC)") (class "Default")
      (node (ref "D1") (pin "C") (pinfunction "C_C") (pintype "passive"))
      (node (ref "J$1") (pin "1") (pinfunction "-12V_1") (pintype "bidirectional"))
      (node (ref "J$1") (pin "2") (pinfunction "-12V_2") (pintype "bidirectional"))
    )
    (net (code "45") (name "Net-(D2-PadA)") (class "Default")
      (node (ref "D2") (pin "A") (pinfunction "A_A") (pintype "passive"))
      (node (ref "J$1") (pin "10") (pinfunction "+12V_10") (pintype "bidirectional"))
      (node (ref "J$1") (pin "9") (pinfunction "+12V_9") (pintype "bidirectional"))
    )
    (net (code "46") (name "Net-(IC1A--IN)") (class "Default")
      (node (ref "C6") (pin "2") (pinfunction "2_2") (pintype "passive"))
      (node (ref "IC1") (pin "2") (pinfunction "-IN_2") (pintype "input"))
      (node (ref "R10") (pin "1") (pinfunction "1_1") (pintype "passive"))
      (node (ref "R4") (pin "2") (pinfunction "2_2") (pintype "passive"))
    )
    (net (code "47") (name "Net-(IC1A-OUT)") (class "Default")
      (node (ref "C6") (pin "1") (pinfunction "1_1") (pintype "passive"))
      (node (ref "IC1") (pin "1") (pinfunction "OUT_1") (pintype "output"))
      (node (ref "R3") (pin "2") (pinfunction "2_2") (pintype "passive"))
    )
    (net (code "48") (name "Net-(IC1B--IN)") (class "Default")
      (node (ref "C12") (pin "2") (pinfunction "2_2") (pintype "passive"))
      (node (ref "IC1") (pin "6") (pinfunction "-IN_6") (pintype "input"))
      (node (ref "R8") (pin "2") (pinfunction "2_2") (pintype "passive"))
      (node (ref "R9") (pin "1") (pinfunction "1_1") (pintype "passive"))
    )
    (net (code "49") (name "Net-(IC1B-OUT)") (class "Default")
      (node (ref "C12") (pin "1") (pinfunction "1_1") (pintype "passive"))
      (node (ref "IC1") (pin "7") (pinfunction "OUT_7") (pintype "output"))
      (node (ref "R6") (pin "2") (pinfunction "2_2") (pintype "passive"))
    )
    (net (code "50") (name "Net-(IC2A--IN)") (class "Default")
      (node (ref "C5") (pin "2") (pinfunction "2_2") (pintype "passive"))
      (node (ref "IC2") (pin "2") (pinfunction "-IN_2") (pintype "input"))
      (node (ref "R11") (pin "1") (pinfunction "1_1") (pintype "passive"))
      (node (ref "R2") (pin "2") (pinfunction "2_2") (pintype "passive"))
    )
    (net (code "51") (name "Net-(IC2A-OUT)") (class "Default")
      (node (ref "C5") (pin "1") (pinfunction "1_1") (pintype "passive"))
      (node (ref "IC2") (pin "1") (pinfunction "OUT_1") (pintype "output"))
      (node (ref "R1") (pin "2") (pinfunction "2_2") (pintype "passive"))
    )
    (net (code "52") (name "Net-(IC2B--IN)") (class "Default")
      (node (ref "C11") (pin "2") (pinfunction "2_2") (pintype "passive"))
      (node (ref "IC2") (pin "6") (pinfunction "-IN_6") (pintype "input"))
      (node (ref "R12") (pin "1") (pinfunction "1_1") (pintype "passive"))
      (node (ref "R7") (pin "2") (pinfunction "2_2") (pintype "passive"))
    )
    (net (code "53") (name "Net-(IC2B-OUT)") (class "Default")
      (node (ref "C11") (pin "1") (pinfunction "1_1") (pintype "passive"))
      (node (ref "IC2") (pin "7") (pinfunction "OUT_7") (pintype "output"))
      (node (ref "R5") (pin "2") (pinfunction "2_2") (pintype "passive"))
    )
    (net (code "54") (name "Net-(IC4A--IN)") (class "Default")
      (node (ref "C31") (pin "2") (pinfunction "2_2") (pintype "passive"))
      (node (ref "IC4") (pin "2") (pinfunction "-IN_2") (pintype "input"))
      (node (ref "R28") (pin "1") (pinfunction "1_1") (pintype "passive"))
      (node (ref "R29") (pin "1") (pinfunction "1_1") (pintype "passive"))
      (node (ref "R30") (pin "2") (pinfunction "2_2") (pintype "passive"))
    )
    (net (code "55") (name "Net-(IC4A-OUT)") (class "Default")
      (node (ref "C31") (pin "1") (pinfunction "1_1") (pintype "passive"))
      (node (ref "IC4") (pin "1") (pinfunction "OUT_1") (pintype "output"))
      (node (ref "R23") (pin "2") (pinfunction "2_2") (pintype "passive"))
      (node (ref "R30") (pin "1") (pinfunction "1_1") (pintype "passive"))
    )
    (net (code "56") (name "Net-(IC4B--IN)") (class "Default")
      (node (ref "C32") (pin "2") (pinfunction "2_2") (pintype "passive"))
      (node (ref "IC4") (pin "6") (pinfunction "-IN_6") (pintype "input"))
      (node (ref "R19") (pin "1") (pinfunction "1_1") (pintype "passive"))
      (node (ref "R20") (pin "2") (pinfunction "2_2") (pintype "passive"))
      (node (ref "R21") (pin "1") (pinfunction "1_1") (pintype "passive"))
    )
    (net (code "57") (name "Net-(IC4B-OUT)") (class "Default")
      (node (ref "C32") (pin "1") (pinfunction "1_1") (pintype "passive"))
      (node (ref "IC4") (pin "7") (pinfunction "OUT_7") (pintype "output"))
      (node (ref "R20") (pin "1") (pinfunction "1_1") (pintype "passive"))
      (node (ref "R25") (pin "2") (pinfunction "2_2") (pintype "passive"))
    )
    (net (code "58") (name "Net-(IC5A--IN)") (class "Default")
      (node (ref "C35") (pin "2") (pinfunction "2_2") (pintype "passive"))
      (node (ref "IC5") (pin "2") (pinfunction "-IN_2") (pintype "input"))
      (node (ref "R36") (pin "2") (pinfunction "2_2") (pintype "passive"))
      (node (ref "R37") (pin "1") (pinfunction "1_1") (pintype "passive"))
      (node (ref "R42") (pin "1") (pinfunction "1_1") (pintype "passive"))
    )
    (net (code "59") (name "Net-(IC5A-OUT)") (class "Default")
      (node (ref "C35") (pin "1") (pinfunction "1_1") (pintype "passive"))
      (node (ref "IC5") (pin "1") (pinfunction "OUT_1") (pintype "output"))
      (node (ref "R36") (pin "1") (pinfunction "1_1") (pintype "passive"))
      (node (ref "R41") (pin "2") (pinfunction "2_2") (pintype "passive"))
    )
    (net (code "60") (name "Net-(IC5B--IN)") (class "Default")
      (node (ref "C34") (pin "2") (pinfunction "2_2") (pintype "passive"))
      (node (ref "IC5") (pin "6") (pinfunction "-IN_6") (pintype "input"))
      (node (ref "R31") (pin "1") (pinfunction "1_1") (pintype "passive"))
      (node (ref "R32") (pin "2") (pinfunction "2_2") (pintype "passive"))
      (node (ref "R39") (pin "1") (pinfunction "1_1") (pintype "passive"))
    )
    (net (code "61") (name "Net-(IC5B-OUT)") (class "Default")
      (node (ref "C34") (pin "1") (pinfunction "1_1") (pintype "passive"))
      (node (ref "IC5") (pin "7") (pinfunction "OUT_7") (pintype "output"))
      (node (ref "R32") (pin "1") (pinfunction "1_1") (pintype "passive"))
      (node (ref "R33") (pin "2") (pinfunction "2_2") (pintype "passive"))
    )
    (net (code "62") (name "Net-(IC7--IN)") (class "Default")
      (node (ref "IC7") (pin "3") (pinfunction "-IN_3") (pintype "input"))
      (node (ref "R14") (pin "1") (pinfunction "1_1") (pintype "passive"))
      (node (ref "R16") (pin "2") (pinfunction "2_2") (pintype "passive"))
    )
    (net (code "63") (name "Net-(IC7-OUT)") (class "Default")
      (node (ref "IC7") (pin "4") (pinfunction "OUT_4") (pintype "output"))
      (node (ref "R14") (pin "2") (pinfunction "2_2") (pintype "passive"))
      (node (ref "R45") (pin "1") (pinfunction "1_1") (pintype "passive"))
    )
    (net (code "64") (name "Net-(Q1-B)") (class "Default")
      (node (ref "Q1") (pin "1") (pinfunction "B_1") (pintype "passive"))
      (node (ref "R22") (pin "1") (pinfunction "1_1") (pintype "passive"))
      (node (ref "R24") (pin "1") (pinfunction "1_1") (pintype "passive"))
    )
    (net (code "65") (name "Net-(Q2-B)") (class "Default")
      (node (ref "Q2") (pin "1") (pinfunction "B_1") (pintype "passive"))
      (node (ref "R26") (pin "1") (pinfunction "1_1") (pintype "passive"))
      (node (ref "R27") (pin "1") (pinfunction "1_1") (pintype "passive"))
    )
    (net (code "66") (name "Net-(Q3-B)") (class "Default")
      (node (ref "Q3") (pin "1") (pinfunction "B_1") (pintype "passive"))
      (node (ref "R34") (pin "1") (pinfunction "1_1") (pintype "passive"))
      (node (ref "R35") (pin "1") (pinfunction "1_1") (pintype "passive"))
    )
    (net (code "67") (name "Net-(Q4-B)") (class "Default")
      (node (ref "Q4") (pin "1") (pinfunction "B_1") (pintype "passive"))
      (node (ref "R38") (pin "1") (pinfunction "1_1") (pintype "passive"))
      (node (ref "R40") (pin "1") (pinfunction "1_1") (pintype "passive"))
    )
    (net (code "68") (name "Net-(R15-Pad2)") (class "Default")
      (node (ref "R15") (pin "2") (pinfunction "2_2") (pintype "passive"))
      (node (ref "SW_B") (pin "1") (pinfunction "1_1") (pintype "passive"))
      (node (ref "SW_B") (pin "2") (pinfunction "2_2") (pintype "passive"))
    )
    (net (code "69") (name "Net-(R17-Pad2)") (class "Default")
      (node (ref "R17") (pin "2") (pinfunction "2_2") (pintype "passive"))
      (node (ref "SW_T") (pin "1") (pinfunction "1_1") (pintype "passive"))
      (node (ref "SW_T") (pin "2") (pinfunction "2_2") (pintype "passive"))
    )
    (net (code "70") (name "Net-(R47-Pad2)") (class "Default")
      (node (ref "R47") (pin "2") (pinfunction "2_2") (pintype "passive"))
      (node (ref "SW_VOR") (pin "1") (pinfunction "1_1") (pintype "passive"))
      (node (ref "SW_VOR") (pin "2") (pinfunction "2_2") (pintype "passive"))
    )
    (net (code "71") (name "Net-(TR1-3)") (class "Default")
      (node (ref "R38") (pin "2") (pinfunction "2_2") (pintype "passive"))
      (node (ref "TR1") (pin "P3") (pinfunction "3_P3") (pintype "passive"))
    )
    (net (code "72") (name "Net-(TR2-3)") (class "Default")
      (node (ref "R34") (pin "2") (pinfunction "2_2") (pintype "passive"))
      (node (ref "TR2") (pin "P3") (pinfunction "3_P3") (pintype "passive"))
    )
    (net (code "73") (name "Net-(TR3-3)") (class "Default")
      (node (ref "R26") (pin "2") (pinfunction "2_2") (pintype "passive"))
      (node (ref "TR3") (pin "P3") (pinfunction "3_P3") (pintype "passive"))
    )
    (net (code "74") (name "Net-(TR4-3)") (class "Default")
      (node (ref "R24") (pin "2") (pinfunction "2_2") (pintype "passive"))
      (node (ref "TR4") (pin "P3") (pinfunction "3_P3") (pintype "passive"))
    )
    (net (code "75") (name "Net-(U1-~{RST})") (class "Default")
      (node (ref "R43") (pin "1") (pinfunction "1_1") (pintype "passive"))
      (node (ref "U1") (pin "13") (pinfunction "~{RST}_13") (pintype "input"))
    )
    (net (code "76") (name "Net-(U2-EN)") (class "Default")
      (node (ref "C24") (pin "1") (pinfunction "1_1") (pintype "passive"))
      (node (ref "C25") (pin "1") (pinfunction "1_1") (pintype "passive"))
      (node (ref "L1") (pin "2") (pinfunction "2_2") (pintype "passive"))
      (node (ref "U2") (pin "1") (pinfunction "VIN_1") (pintype "input"))
      (node (ref "U2") (pin "3") (pinfunction "EN_3") (pintype "input"))
    )
    (net (code "77") (name "RESET_PAD") (class "Default")
      (node (ref "IC6") (pin "2") (pinfunction "~{RESET}_2") (pintype "bidirectional"))
      (node (ref "TEENSY3.2") (pin "RESET_PAD") (pinfunction "RESET_PAD_RESET_PAD") (pintype "bidirectional"))
    )
    (net (code "78") (name "T_DAC") (class "Default")
      (node (ref "IC7") (pin "1") (pinfunction "+IN_1") (pintype "input"))
      (node (ref "TEENSY3.2") (pin "RESET/DAC") (pinfunction "A14/DAC_RESET/DAC") (pintype "bidirectional"))
    )
    (net (code "79") (name "USB_D+") (class "Default")
      (node (ref "TEENSY3.2") (pin "D+") (pinfunction "USB/D+_D+") (pintype "bidirectional"))
      (node (ref "U$1") (pin "D+") (pinfunction "D+_D+") (pintype "bidirectional"))
    )
    (net (code "80") (name "USB_D-") (class "Default")
      (node (ref "TEENSY3.2") (pin "D-") (pinfunction "USB/D-_D-") (pintype "bidirectional"))
      (node (ref "U$1") (pin "D-") (pinfunction "D-_D-") (pintype "bidirectional"))
    )
    (net (code "81") (name "VCC") (class "Default")
      (node (ref "C18") (pin "2") (pinfunction "2_2") (pintype "passive"))
      (node (ref "C2") (pin "+") (pinfunction "+_+") (pintype "passive"))
      (node (ref "C4") (pin "+") (pinfunction "+_+") (pintype "passive"))
      (node (ref "C7") (pin "1") (pinfunction "1_1") (pintype "passive"))
      (node (ref "C8") (pin "1") (pinfunction "1_1") (pintype "passive"))
      (node (ref "D2") (pin "C") (pinfunction "C_C") (pintype "passive"))
      (node (ref "IC1") (pin "8") (pinfunction "V+_8") (pintype "power_in"))
      (node (ref "IC2") (pin "8") (pinfunction "V+_8") (pintype "power_in"))
      (node (ref "IC7") (pin "5") (pinfunction "V+_5") (pintype "power_in"))
      (node (ref "U3") (pin "3") (pinfunction "IN_3") (pintype "input"))
    )
    (net (code "82") (name "VEE") (class "Default")
      (node (ref "C10") (pin "2") (pinfunction "2_2") (pintype "passive"))
      (node (ref "C19") (pin "2") (pinfunction "2_2") (pintype "passive"))
      (node (ref "C28") (pin "1") (pinfunction "1_1") (pintype "passive"))
      (node (ref "C3") (pin "-") (pinfunction "-_-") (pintype "passive"))
      (node (ref "C9") (pin "2") (pinfunction "2_2") (pintype "passive"))
      (node (ref "D1") (pin "A") (pinfunction "A_A") (pintype "passive"))
      (node (ref "IC1") (pin "4") (pinfunction "V-_4") (pintype "power_in"))
      (node (ref "IC2") (pin "4") (pinfunction "V-_4") (pintype "power_in"))
      (node (ref "IC7") (pin "2") (pinfunction "V-_2") (pintype "power_in"))
      (node (ref "R18") (pin "1") (pinfunction "1_1") (pintype "passive"))
    )
    (net (code "83") (name "V_BIAS") (class "Default")
      (node (ref "C15") (pin "1") (pinfunction "1_1") (pintype "passive"))
      (node (ref "C40") (pin "+") (pinfunction "+_+") (pintype "passive"))
      (node (ref "IC1") (pin "3") (pinfunction "+IN_3") (pintype "input"))
      (node (ref "IC1") (pin "5") (pinfunction "+IN_5") (pintype "input"))
      (node (ref "IC2") (pin "3") (pinfunction "+IN_3") (pintype "input"))
      (node (ref "IC2") (pin "5") (pinfunction "+IN_5") (pintype "input"))
      (node (ref "R44") (pin "2") (pinfunction "2_2") (pintype "passive"))
    )
    (net (code "84") (name "unconnected-(CV_A-2-PadP2)") (class "Default")
      (node (ref "CV_A") (pin "P2") (pinfunction "2_P2") (pintype "passive"))
    )
    (net (code "85") (name "unconnected-(CV_B-2-PadP2)") (class "Default")
      (node (ref "CV_B") (pin "P2") (pinfunction "2_P2") (pintype "passive"))
    )
    (net (code "86") (name "unconnected-(CV_C-2-PadP2)") (class "Default")
      (node (ref "CV_C") (pin "P2") (pinfunction "2_P2") (pintype "passive"))
    )
    (net (code "87") (name "unconnected-(CV_D-2-PadP2)") (class "Default")
      (node (ref "CV_D") (pin "P2") (pinfunction "2_P2") (pintype "passive"))
    )
    (net (code "88") (name "unconnected-(U$1-PadVCC)") (class "Default")
      (node (ref "U$1") (pin "VCC") (pinfunction "VCC_VCC") (pintype "bidirectional"))
    )
  )
)
